# PCB-3SLIDER45.net
KiCad netlist of a schematic drawn in EAGLE
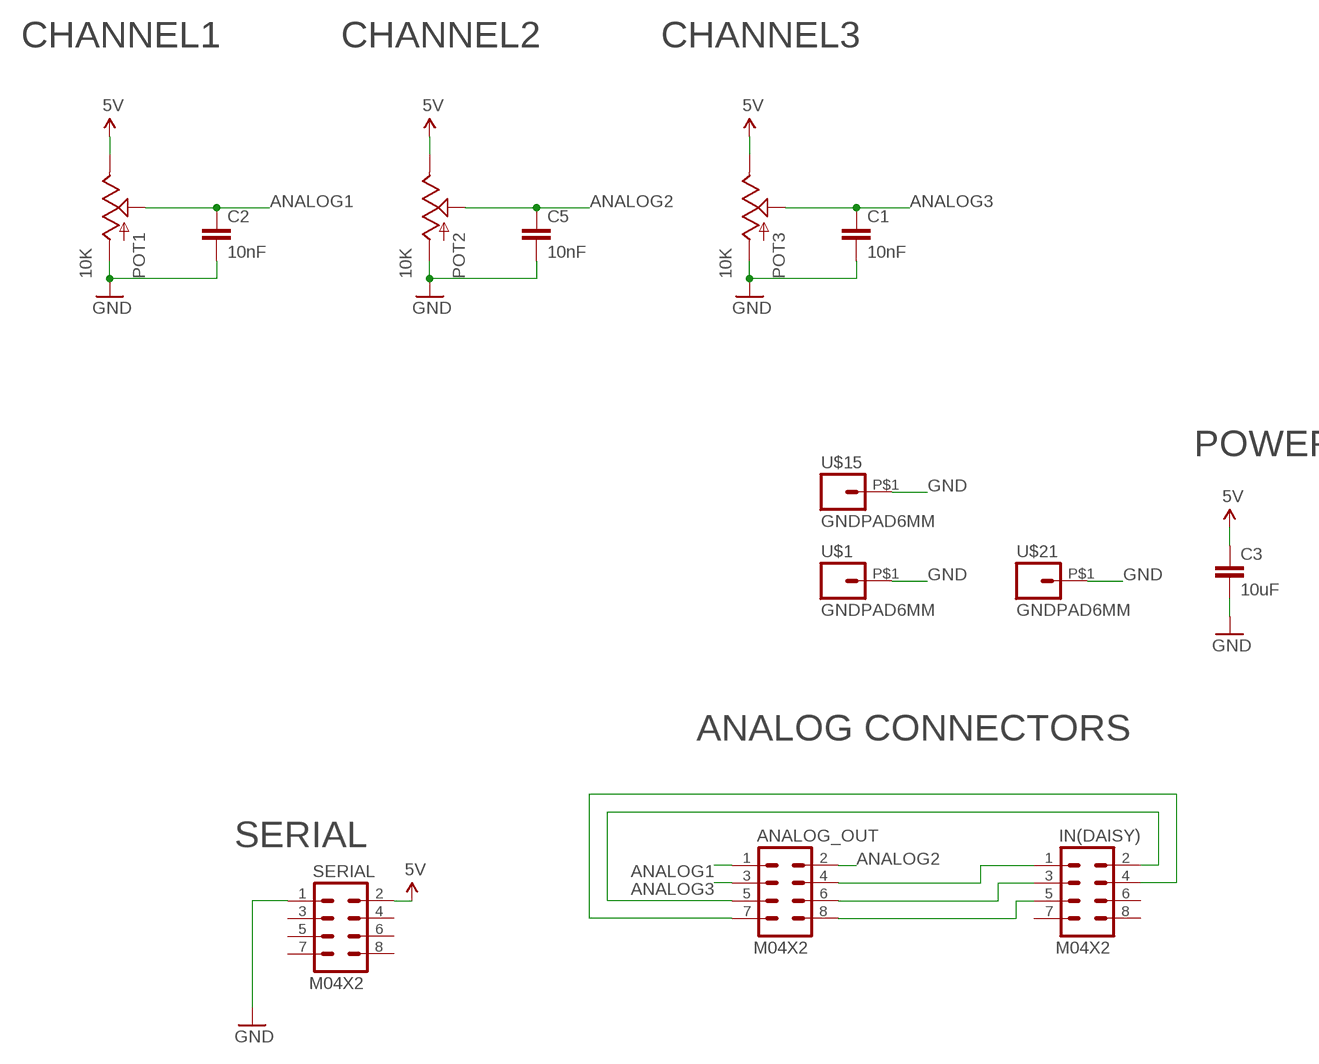
[diagram p0: schematic, sheet 1]

(export (version "E")
  (design (tool "Eeschema 10.0.6"))
  (components
    (comp (ref "ANALOG_OUT")
      (value "M04X2")
      (footprint "eagle-import:2X4")
      (libsource (lib "eagle-import") (part "M04X2"))
    )
    (comp (ref "C1")
      (value "10nF")
      (footprint "eagle-import:0603-CAP")
      (libsource (lib "eagle-import") (part "CAP0603-CAP"))
    )
    (comp (ref "C2")
      (value "10nF")
      (footprint "eagle-import:0603-CAP")
      (libsource (lib "eagle-import") (part "CAP0603-CAP"))
    )
    (comp (ref "C3")
      (value "10uF")
      (footprint "eagle-import:0805")
      (libsource (lib "eagle-import") (part "CAP0805"))
    )
    (comp (ref "C5")
      (value "10nF")
      (footprint "eagle-import:0603-CAP")
      (libsource (lib "eagle-import") (part "CAP0603-CAP"))
    )
    (comp (ref "IN(DAISY)")
      (value "M04X2")
      (footprint "eagle-import:2X4")
      (libsource (lib "eagle-import") (part "M04X2"))
    )
    (comp (ref "POT1")
      (value "10K")
      (footprint "eagle-import:SLIDER45")
      (libsource (lib "eagle-import") (part "SLIDER45"))
    )
    (comp (ref "POT2")
      (value "10K")
      (footprint "eagle-import:SLIDER45")
      (libsource (lib "eagle-import") (part "SLIDER45"))
    )
    (comp (ref "POT3")
      (value "10K")
      (footprint "eagle-import:SLIDER45")
      (libsource (lib "eagle-import") (part "SLIDER45"))
    )
    (comp (ref "SERIAL")
      (value "M04X2")
      (footprint "eagle-import:2X4")
      (libsource (lib "eagle-import") (part "M04X2"))
    )
    (comp (ref "U$1")
      (value "GNDPAD6MM")
      (footprint "eagle-import:3.2MMPAD6MM")
      (libsource (lib "eagle-import") (part "GNDPAD6MM"))
    )
    (comp (ref "U$15")
      (value "GNDPAD6MM")
      (footprint "eagle-import:3.2MMPAD6MM")
      (libsource (lib "eagle-import") (part "GNDPAD6MM"))
    )
    (comp (ref "U$21")
      (value "GNDPAD6MM")
      (footprint "eagle-import:3.2MMPAD6MM")
      (libsource (lib "eagle-import") (part "GNDPAD6MM"))
    )
  )
  (nets
    (net (code "1") (name "5V") (class "Default")
      (node (ref "C3") (pin "1") (pinfunction "1_1") (pintype "passive"))
      (node (ref "POT1") (pin "1") (pinfunction "E_1") (pintype "passive"))
      (node (ref "POT2") (pin "1") (pinfunction "E_1") (pintype "passive"))
      (node (ref "POT3") (pin "1") (pinfunction "E_1") (pintype "passive"))
      (node (ref "SERIAL") (pin "2") (pinfunction "2_2") (pintype "passive"))
    )
    (net (code "2") (name "ANALOG1") (class "Default")
      (node (ref "ANALOG_OUT") (pin "1") (pinfunction "1_1") (pintype "passive"))
      (node (ref "C2") (pin "1") (pinfunction "1_1") (pintype "passive"))
      (node (ref "POT1") (pin "2A") (pinfunction "S_2A") (pintype "passive"))
    )
    (net (code "3") (name "ANALOG2") (class "Default")
      (node (ref "ANALOG_OUT") (pin "2") (pinfunction "2_2") (pintype "passive"))
      (node (ref "C5") (pin "1") (pinfunction "1_1") (pintype "passive"))
      (node (ref "POT2") (pin "2A") (pinfunction "S_2A") (pintype "passive"))
    )
    (net (code "4") (name "ANALOG3") (class "Default")
      (node (ref "ANALOG_OUT") (pin "3") (pinfunction "3_3") (pintype "passive"))
      (node (ref "C1") (pin "1") (pinfunction "1_1") (pintype "passive"))
      (node (ref "POT3") (pin "2A") (pinfunction "S_2A") (pintype "passive"))
    )
    (net (code "5") (name "GND") (class "Default")
      (node (ref "C1") (pin "2") (pinfunction "2_2") (pintype "passive"))
      (node (ref "C2") (pin "2") (pinfunction "2_2") (pintype "passive"))
      (node (ref "C3") (pin "2") (pinfunction "2_2") (pintype "passive"))
      (node (ref "C5") (pin "2") (pinfunction "2_2") (pintype "passive"))
      (node (ref "POT1") (pin "3") (pinfunction "A_3") (pintype "passive"))
      (node (ref "POT2") (pin "3") (pinfunction "A_3") (pintype "passive"))
      (node (ref "POT3") (pin "3") (pinfunction "A_3") (pintype "passive"))
      (node (ref "SERIAL") (pin "1") (pinfunction "1_1") (pintype "passive"))
      (node (ref "U$1") (pin "P$1") (pinfunction "1_P$1") (pintype "passive"))
      (node (ref "U$15") (pin "P$1") (pinfunction "1_P$1") (pintype "passive"))
      (node (ref "U$21") (pin "P$1") (pinfunction "1_P$1") (pintype "passive"))
    )
    (net (code "6") (name "Net-(ANALOG_OUT-Pad4)") (class "Default")
      (node (ref "ANALOG_OUT") (pin "4") (pinfunction "4_4") (pintype "passive"))
      (node (ref "IN(DAISY)") (pin "1") (pinfunction "1_1") (pintype "passive"))
    )
    (net (code "7") (name "Net-(ANALOG_OUT-Pad5)") (class "Default")
      (node (ref "ANALOG_OUT") (pin "5") (pinfunction "5_5") (pintype "passive"))
      (node (ref "IN(DAISY)") (pin "2") (pinfunction "2_2") (pintype "passive"))
    )
    (net (code "8") (name "Net-(ANALOG_OUT-Pad6)") (class "Default")
      (node (ref "ANALOG_OUT") (pin "6") (pinfunction "6_6") (pintype "passive"))
      (node (ref "IN(DAISY)") (pin "3") (pinfunction "3_3") (pintype "passive"))
    )
    (net (code "9") (name "Net-(ANALOG_OUT-Pad7)") (class "Default")
      (node (ref "ANALOG_OUT") (pin "7") (pinfunction "7_7") (pintype "passive"))
      (node (ref "IN(DAISY)") (pin "4") (pinfunction "4_4") (pintype "passive"))
    )
    (net (code "10") (name "Net-(ANALOG_OUT-Pad8)") (class "Default")
      (node (ref "ANALOG_OUT") (pin "8") (pinfunction "8_8") (pintype "passive"))
      (node (ref "IN(DAISY)") (pin "5") (pinfunction "5_5") (pintype "passive"))
    )
    (net (code "11") (name "unconnected-(IN(DAISY)-Pad6)") (class "Default")
      (node (ref "IN(DAISY)") (pin "6") (pinfunction "6_6") (pintype "passive"))
    )
    (net (code "12") (name "unconnected-(IN(DAISY)-Pad7)") (class "Default")
      (node (ref "IN(DAISY)") (pin "7") (pinfunction "7_7") (pintype "passive"))
    )
    (net (code "13") (name "unconnected-(IN(DAISY)-Pad8)") (class "Default")
      (node (ref "IN(DAISY)") (pin "8") (pinfunction "8_8") (pintype "passive"))
    )
    (net (code "14") (name "unconnected-(SERIAL-Pad3)") (class "Default")
      (node (ref "SERIAL") (pin "3") (pinfunction "3_3") (pintype "passive"))
    )
    (net (code "15") (name "unconnected-(SERIAL-Pad4)") (class "Default")
      (node (ref "SERIAL") (pin "4") (pinfunction "4_4") (pintype "passive"))
    )
    (net (code "16") (name "unconnected-(SERIAL-Pad5)") (class "Default")
      (node (ref "SERIAL") (pin "5") (pinfunction "5_5") (pintype "passive"))
    )
    (net (code "17") (name "unconnected-(SERIAL-Pad6)") (class "Default")
      (node (ref "SERIAL") (pin "6") (pinfunction "6_6") (pintype "passive"))
    )
    (net (code "18") (name "unconnected-(SERIAL-Pad7)") (class "Default")
      (node (ref "SERIAL") (pin "7") (pinfunction "7_7") (pintype "passive"))
    )
    (net (code "19") (name "unconnected-(SERIAL-Pad8)") (class "Default")
      (node (ref "SERIAL") (pin "8") (pinfunction "8_8") (pintype "passive"))
    )
  )
)
